# GaN-amplifier.net
KiCad netlist of a schematic drawn in EAGLE
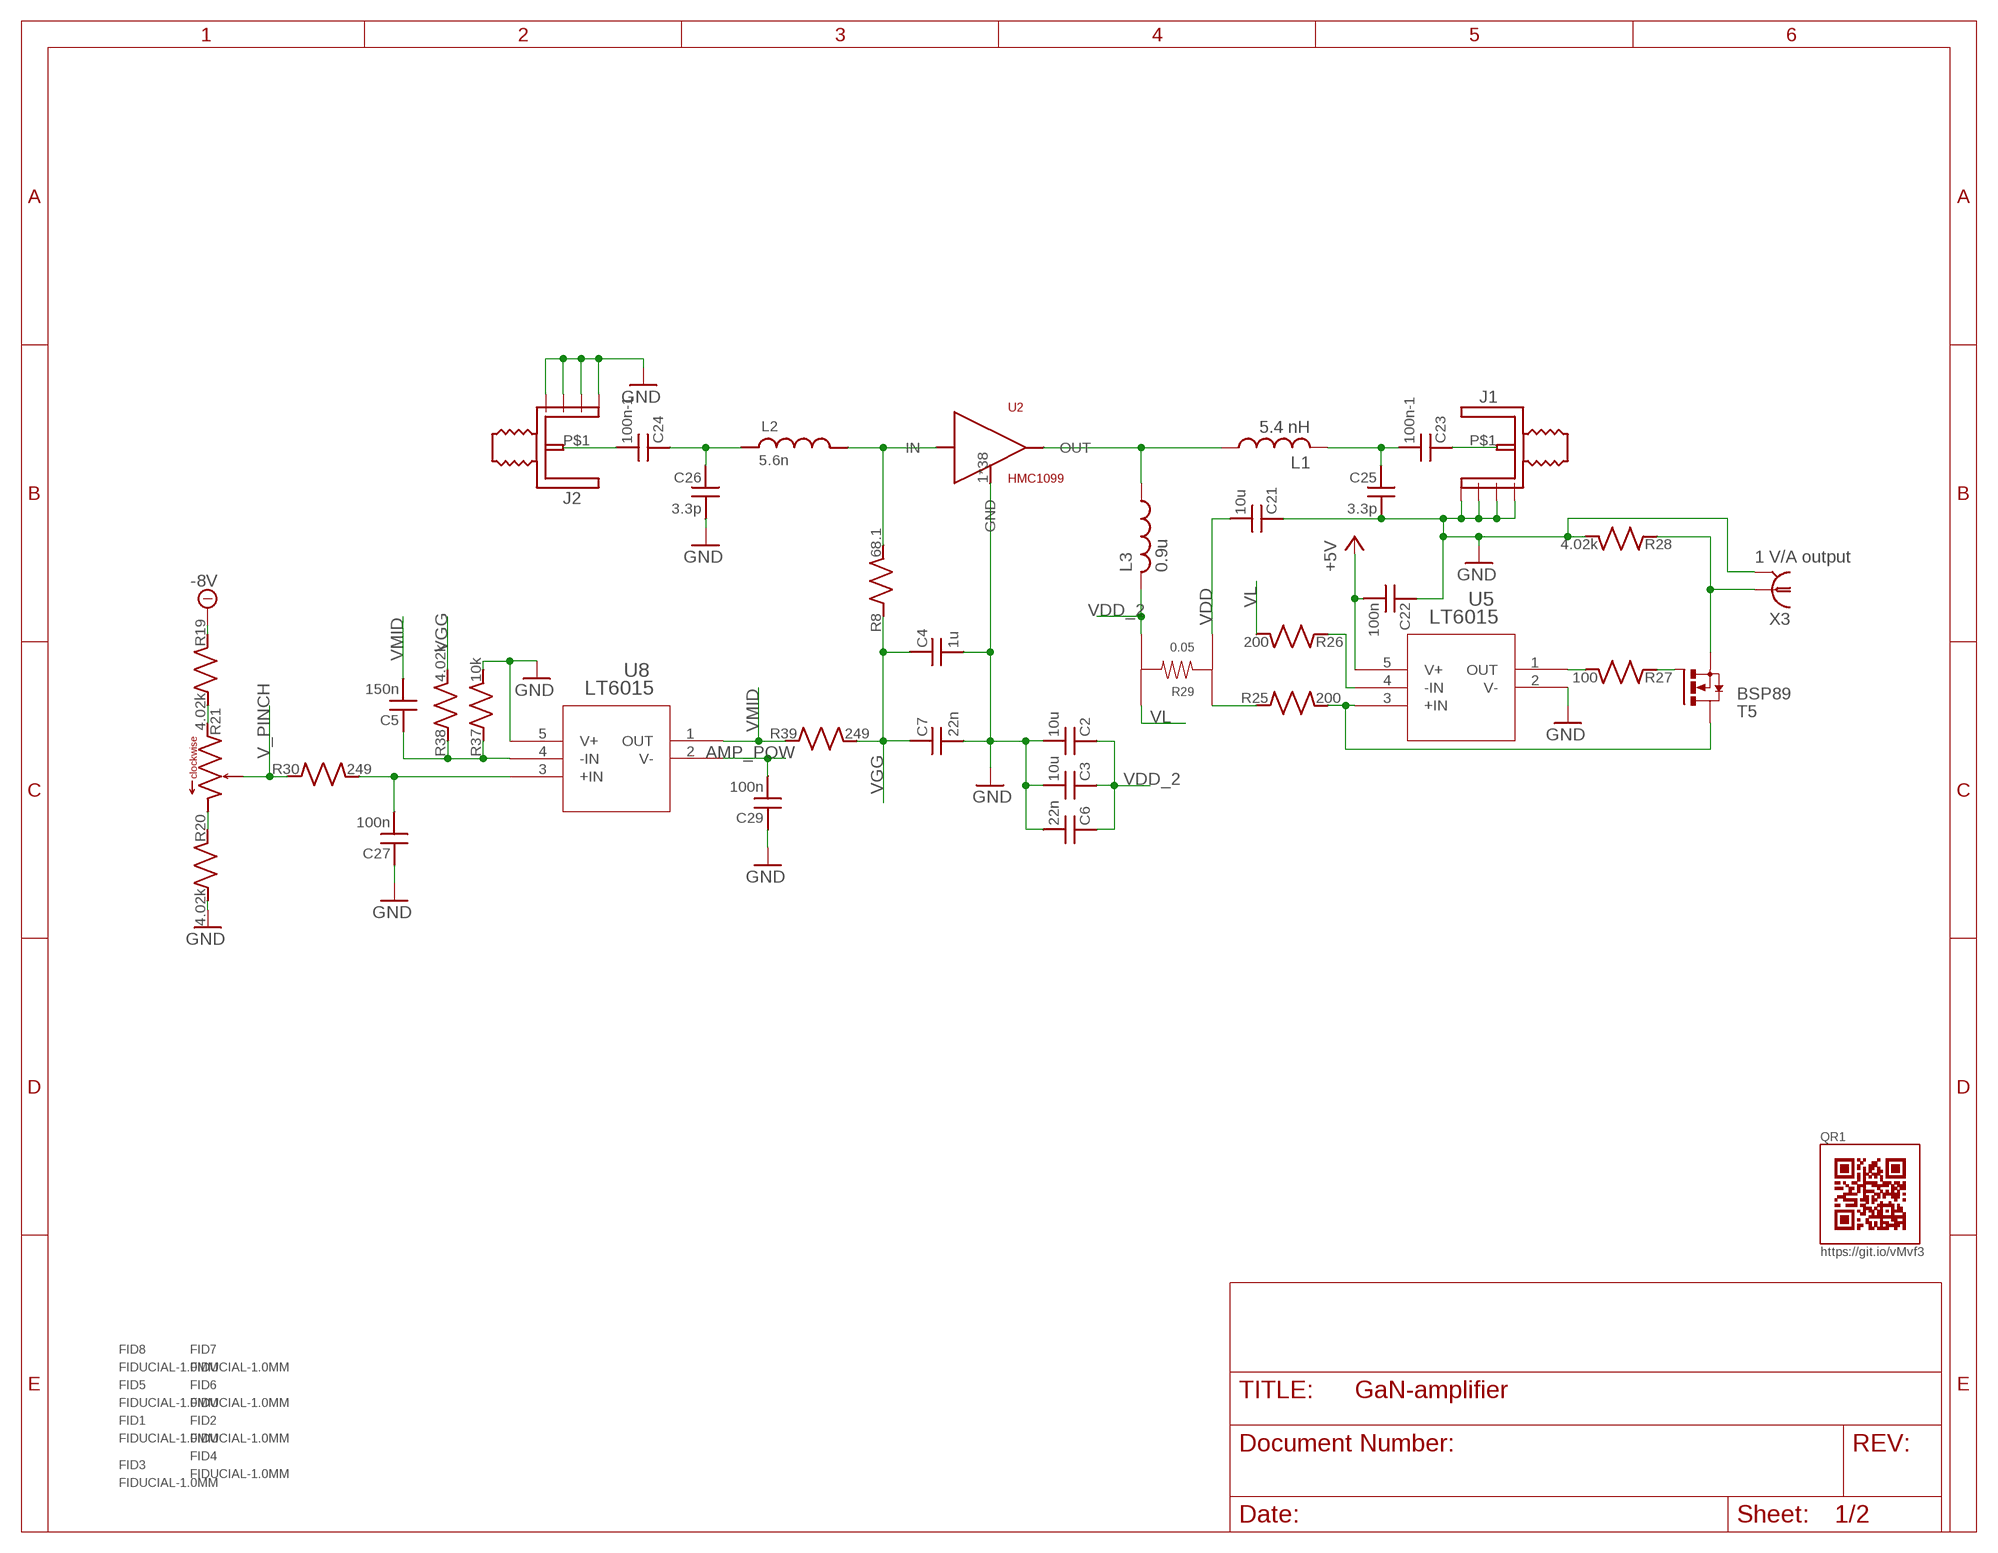
[diagram p0: schematic, sheet 1]
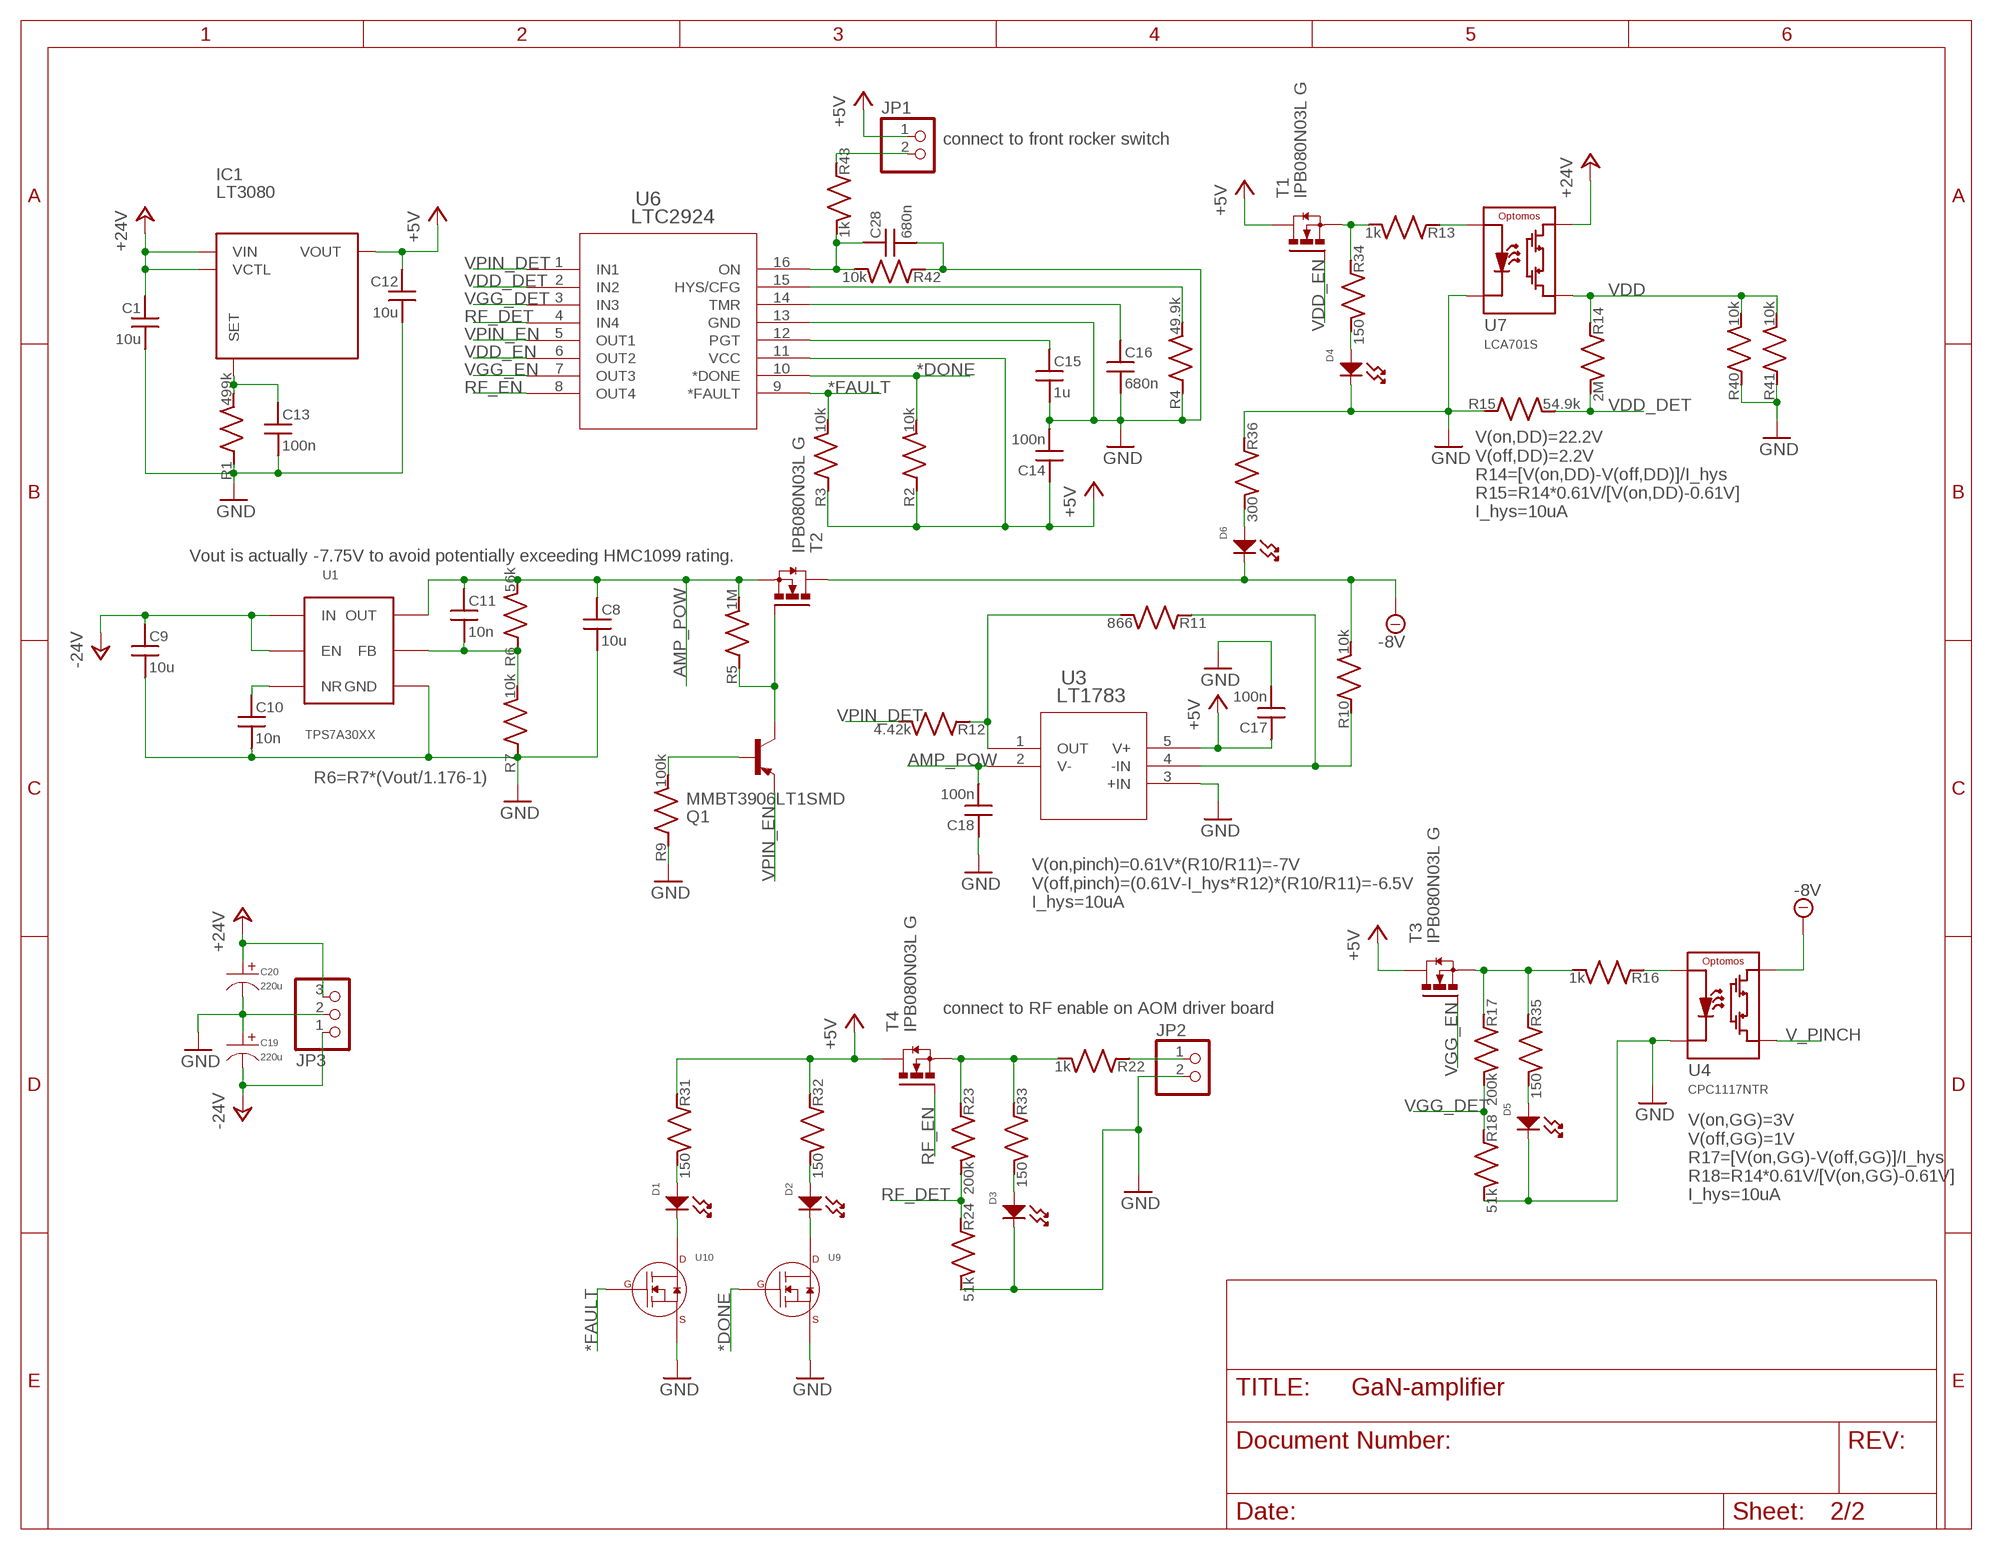
[diagram p1: schematic, sheet 2]

(export (version "E")
  (design (tool "Eeschema 10.0.6"))
  (components
    (comp (ref "C1")
      (value "10u")
      (footprint "eagle-import:C_MLCC_1210")
      (fields (field (name "PARTNO") "CL32B106KBJNNNE"))
      (libsource (lib "eagle-import") (part "C_MLCC_SMDCMLCC_1210"))
    )
    (comp (ref "C8")
      (value "10u")
      (footprint "eagle-import:C_MLCC_1210")
      (fields (field (name "PARTNO") "CL32B106KBJNNNE"))
      (libsource (lib "eagle-import") (part "C_MLCC_SMDCMLCC_1210"))
    )
    (comp (ref "C9")
      (value "10u")
      (footprint "eagle-import:C_MLCC_1210")
      (fields (field (name "PARTNO") "CL32B106KBJNNNE"))
      (libsource (lib "eagle-import") (part "C_MLCC_SMDCMLCC_1210"))
    )
    (comp (ref "C10")
      (value "10n")
      (footprint "eagle-import:C_MLCC_0402")
      (fields (field (name "PARTNO") "CL05B103KB5NNNC"))
      (libsource (lib "eagle-import") (part "C_MLCC_SMDCMLCC_0402"))
    )
    (comp (ref "C11")
      (value "10n")
      (footprint "eagle-import:C_MLCC_0402")
      (fields (field (name "PARTNO") "CL05B103KB5NNNC"))
      (libsource (lib "eagle-import") (part "C_MLCC_SMDCMLCC_0402"))
    )
    (comp (ref "C12")
      (value "10u")
      (footprint "eagle-import:C_MLCC_1210")
      (fields (field (name "PARTNO") "CL32B106KBJNNNE"))
      (libsource (lib "eagle-import") (part "C_MLCC_SMDCMLCC_1210"))
    )
    (comp (ref "C13")
      (value "100n")
      (footprint "eagle-import:C_MLCC_0603")
      (fields (field (name "PARTNO") "CL10B104KB8SFNC"))
      (libsource (lib "eagle-import") (part "C_MLCC_SMDCMLCC_0603"))
    )
    (comp (ref "C14")
      (value "100n")
      (footprint "eagle-import:C_MLCC_0603")
      (fields (field (name "PARTNO") "CL10B104KB8SFNC"))
      (libsource (lib "eagle-import") (part "C_MLCC_SMDCMLCC_0603"))
    )
    (comp (ref "C15")
      (value "1u")
      (footprint "eagle-import:C_MLCC_0603")
      (fields (field (name "PARTNO") "CL10B105KA8NNNC"))
      (libsource (lib "eagle-import") (part "C_MLCC_SMDCMLCC_0603"))
    )
    (comp (ref "C16")
      (value "680n")
      (footprint "eagle-import:C_MLCC_0603")
      (fields (field (name "PARTNO") "CL10B684KO8NFNC"))
      (libsource (lib "eagle-import") (part "C_MLCC_SMDCMLCC_0603"))
    )
    (comp (ref "C17")
      (value "100n")
      (footprint "eagle-import:C_MLCC_0603")
      (fields (field (name "PARTNO") "CL10B104KB8SFNC"))
      (libsource (lib "eagle-import") (part "C_MLCC_SMDCMLCC_0603"))
    )
    (comp (ref "C18")
      (value "100n")
      (footprint "eagle-import:C_MLCC_0603")
      (fields (field (name "PARTNO") "CL10B104KB8SFNC"))
      (libsource (lib "eagle-import") (part "C_MLCC_SMDCMLCC_0603"))
    )
    (comp (ref "C19")
      (value "220u")
      (footprint "eagle-import:CP10MM")
      (fields (field (name "PARTNO") "MF-CAP-10MM-220uF"))
      (libsource (lib "eagle-import") (part "CAPACITOR_P_10MM"))
    )
    (comp (ref "C20")
      (value "220u")
      (footprint "eagle-import:CP10MM")
      (fields (field (name "PARTNO") "MF-CAP-10MM-220uF"))
      (libsource (lib "eagle-import") (part "CAPACITOR_P_10MM"))
    )
    (comp (ref "C28")
      (value "680n")
      (footprint "eagle-import:C_MLCC_0603")
      (fields (field (name "PARTNO") "CL10B684KO8NFNC"))
      (libsource (lib "eagle-import") (part "C_MLCC_SMDCMLCC_0603"))
    )
    (comp (ref "D1")
      (value "LED_SINGLE-0603-GREEN")
      (footprint "eagle-import:LED0603")
      (fields (field (name "HOUSEPART") "YES") (field (name "MPN") "MF-LED-0603-GREEN"))
      (libsource (lib "eagle-import") (part "LED_SINGLE-0603-GREEN"))
    )
    (comp (ref "D2")
      (value "LED_SINGLE-0603-RED")
      (footprint "eagle-import:LED0603")
      (fields (field (name "HOUSEPART") "YES") (field (name "MPN") "MF-LED-0603-RED"))
      (libsource (lib "eagle-import") (part "LED_SINGLE-0603-RED"))
    )
    (comp (ref "D3")
      (value "LED_SINGLE-0603-GREEN")
      (footprint "eagle-import:LED0603")
      (fields (field (name "HOUSEPART") "YES") (field (name "MPN") "MF-LED-0603-GREEN"))
      (libsource (lib "eagle-import") (part "LED_SINGLE-0603-GREEN"))
    )
    (comp (ref "D4")
      (value "LED_SINGLE-0603-GREEN")
      (footprint "eagle-import:LED0603")
      (fields (field (name "HOUSEPART") "YES") (field (name "MPN") "MF-LED-0603-GREEN"))
      (libsource (lib "eagle-import") (part "LED_SINGLE-0603-GREEN"))
    )
    (comp (ref "D5")
      (value "LED_SINGLE-0603-GREEN")
      (footprint "eagle-import:LED0603")
      (fields (field (name "HOUSEPART") "YES") (field (name "MPN") "MF-LED-0603-GREEN"))
      (libsource (lib "eagle-import") (part "LED_SINGLE-0603-GREEN"))
    )
    (comp (ref "D6")
      (value "LED_SINGLE-0603-GREEN")
      (footprint "eagle-import:LED0603")
      (fields (field (name "HOUSEPART") "YES") (field (name "MPN") "MF-LED-0603-GREEN"))
      (libsource (lib "eagle-import") (part "LED_SINGLE-0603-GREEN"))
    )
    (comp (ref "IC1")
      (value "LT3080")
      (footprint "eagle-import:TO263-5")
      (fields (field (name "PARTNO") "LT3080EQ#PBF"))
      (libsource (lib "eagle-import") (part "LT3080"))
    )
    (comp (ref "JP1")
      (value "PINHD-1X2")
      (footprint "eagle-import:1X02")
      (fields (field (name "PARTNO") "640456-2"))
      (libsource (lib "eagle-import") (part "PINHD-1X2"))
    )
    (comp (ref "JP2")
      (value "PINHD-1X2")
      (footprint "eagle-import:1X02")
      (fields (field (name "PARTNO") "640456-2"))
      (libsource (lib "eagle-import") (part "PINHD-1X2"))
    )
    (comp (ref "JP3")
      (value "PINHD-1X3")
      (footprint "eagle-import:1X03")
      (fields (field (name "PARTNO") "640456-3"))
      (libsource (lib "eagle-import") (part "PINHD-1X3"))
    )
    (comp (ref "Q1")
      (value "MMBT3906LT1SMD")
      (footprint "eagle-import:SOT23-BEC")
      (fields (field (name "PARTNO") "MF-DSC-SOT233-MMBT3906"))
      (libsource (lib "eagle-import") (part "MMBT3906SMDLT1"))
    )
    (comp (ref "R1")
      (value "499k")
      (footprint "eagle-import:R_0603")
      (fields (field (name "PARTNO") "ERJ-3EKF4993V"))
      (libsource (lib "eagle-import") (part "R_SMDR0603"))
    )
    (comp (ref "R2")
      (value "10k")
      (footprint "eagle-import:R_0603")
      (fields (field (name "PARTNO") "ERJ-3EKF1002V"))
      (libsource (lib "eagle-import") (part "R_SMDR0603"))
    )
    (comp (ref "R3")
      (value "10k")
      (footprint "eagle-import:R_0603")
      (fields (field (name "PARTNO") "ERJ-3EKF1002V"))
      (libsource (lib "eagle-import") (part "R_SMDR0603"))
    )
    (comp (ref "R4")
      (value "49.9k")
      (footprint "eagle-import:R_0603")
      (fields (field (name "PARTNO") "ERJ-3EKF4992V"))
      (libsource (lib "eagle-import") (part "R_SMDR0603"))
    )
    (comp (ref "R5")
      (value "1M")
      (footprint "eagle-import:R_0603")
      (fields (field (name "PARTNO") "ERJ-3EKF1004V"))
      (libsource (lib "eagle-import") (part "R_SMDR0603"))
    )
    (comp (ref "R6")
      (value "56k")
      (footprint "eagle-import:R_0402")
      (fields (field (name "PARTNO") "ERJ-2RKF5602X"))
      (libsource (lib "eagle-import") (part "R_SMDR0402"))
    )
    (comp (ref "R7")
      (value "10k")
      (footprint "eagle-import:R_0402")
      (fields (field (name "PARTNO") "ERJ-2RKF1002X"))
      (libsource (lib "eagle-import") (part "R_SMDR0402"))
    )
    (comp (ref "R9")
      (value "100k")
      (footprint "eagle-import:R_0603")
      (fields (field (name "PARTNO") "ERJ-3EKF1003V"))
      (libsource (lib "eagle-import") (part "R_SMDR0603"))
    )
    (comp (ref "R10")
      (value "10k")
      (footprint "eagle-import:R_0603")
      (fields (field (name "PARTNO") "ERJ-3EKF1002V"))
      (libsource (lib "eagle-import") (part "R_SMDR0603"))
    )
    (comp (ref "R11")
      (value "866")
      (footprint "eagle-import:R_0603")
      (fields (field (name "PARTNO") "ERJ-3EKF8660V"))
      (libsource (lib "eagle-import") (part "R_SMDR0603"))
    )
    (comp (ref "R12")
      (value "4.42k")
      (footprint "eagle-import:R_0603")
      (fields (field (name "PARTNO") "ERJ-3EKF4421V"))
      (libsource (lib "eagle-import") (part "R_SMDR0603"))
    )
    (comp (ref "R13")
      (value "1k")
      (footprint "eagle-import:R_0603")
      (fields (field (name "PARTNO") "ERJ-3EKF1001V"))
      (libsource (lib "eagle-import") (part "R_SMDR0603"))
    )
    (comp (ref "R14")
      (value "2M")
      (footprint "eagle-import:R_0603")
      (fields (field (name "PARTNO") "ERJ-3EKF2004V"))
      (libsource (lib "eagle-import") (part "R_SMDR0603"))
    )
    (comp (ref "R15")
      (value "54.9k")
      (footprint "eagle-import:R_0603")
      (fields (field (name "PARTNO") "ERJ-3EKF5492V"))
      (libsource (lib "eagle-import") (part "R_SMDR0603"))
    )
    (comp (ref "R16")
      (value "1k")
      (footprint "eagle-import:R_0603")
      (fields (field (name "PARTNO") "ERJ-3EKF1001V"))
      (libsource (lib "eagle-import") (part "R_SMDR0603"))
    )
    (comp (ref "R17")
      (value "200k")
      (footprint "eagle-import:R_0603")
      (fields (field (name "PARTNO") "ERJ-3EKF2003V"))
      (libsource (lib "eagle-import") (part "R_SMDR0603"))
    )
    (comp (ref "R18")
      (value "51k")
      (footprint "eagle-import:R_0603")
      (fields (field (name "PARTNO") "ERJ-3EKF5102V"))
      (libsource (lib "eagle-import") (part "R_SMDR0603"))
    )
    (comp (ref "R22")
      (value "1k")
      (footprint "eagle-import:R_0603")
      (fields (field (name "PARTNO") "ERJ-3EKF1001V"))
      (libsource (lib "eagle-import") (part "R_SMDR0603"))
    )
    (comp (ref "R23")
      (value "200k")
      (footprint "eagle-import:R_0603")
      (fields (field (name "PARTNO") "ERJ-3EKF2003V"))
      (libsource (lib "eagle-import") (part "R_SMDR0603"))
    )
    (comp (ref "R24")
      (value "51k")
      (footprint "eagle-import:R_0603")
      (fields (field (name "PARTNO") "ERJ-3EKF5102V"))
      (libsource (lib "eagle-import") (part "R_SMDR0603"))
    )
    (comp (ref "R31")
      (value "150")
      (footprint "eagle-import:R_0603")
      (fields (field (name "PARTNO") "ERJ-3EKF1500V"))
      (libsource (lib "eagle-import") (part "R_SMDR0603"))
    )
    (comp (ref "R32")
      (value "150")
      (footprint "eagle-import:R_0603")
      (fields (field (name "PARTNO") "ERJ-3EKF1500V"))
      (libsource (lib "eagle-import") (part "R_SMDR0603"))
    )
    (comp (ref "R33")
      (value "150")
      (footprint "eagle-import:R_0603")
      (fields (field (name "PARTNO") "ERJ-3EKF1500V"))
      (libsource (lib "eagle-import") (part "R_SMDR0603"))
    )
    (comp (ref "R34")
      (value "150")
      (footprint "eagle-import:R_0603")
      (fields (field (name "PARTNO") "ERJ-3EKF1500V"))
      (libsource (lib "eagle-import") (part "R_SMDR0603"))
    )
    (comp (ref "R35")
      (value "150")
      (footprint "eagle-import:R_0603")
      (fields (field (name "PARTNO") "ERJ-3EKF1500V"))
      (libsource (lib "eagle-import") (part "R_SMDR0603"))
    )
    (comp (ref "R36")
      (value "300")
      (footprint "eagle-import:R_0603")
      (fields (field (name "PARTNO") "ERJ-PA3F3000V"))
      (libsource (lib "eagle-import") (part "R_SMDR0603"))
    )
    (comp (ref "R40")
      (value "10k")
      (footprint "eagle-import:R_0603")
      (fields (field (name "PARTNO") "ERJ-3EKF1002V"))
      (libsource (lib "eagle-import") (part "R_SMDR0603"))
    )
    (comp (ref "R41")
      (value "10k")
      (footprint "eagle-import:R_0603")
      (fields (field (name "PARTNO") "ERJ-3EKF1002V"))
      (libsource (lib "eagle-import") (part "R_SMDR0603"))
    )
    (comp (ref "R42")
      (value "10k")
      (footprint "eagle-import:R_0603")
      (fields (field (name "PARTNO") "ERJ-3EKF1002V"))
      (libsource (lib "eagle-import") (part "R_SMDR0603"))
    )
    (comp (ref "R43")
      (value "1k")
      (footprint "eagle-import:R_0603")
      (fields (field (name "PARTNO") "ERJ-3EKF1001V"))
      (libsource (lib "eagle-import") (part "R_SMDR0603"))
    )
    (comp (ref "T1")
      (value "IPB080N03L G")
      (footprint "eagle-import:D2PACK")
      (libsource (lib "eagle-import") (part "IRL3714"))
    )
    (comp (ref "T2")
      (value "IPB080N03L G")
      (footprint "eagle-import:D2PACK")
      (libsource (lib "eagle-import") (part "IRL3714"))
    )
    (comp (ref "T3")
      (value "IPB080N03L G")
      (footprint "eagle-import:D2PACK")
      (libsource (lib "eagle-import") (part "IRL3714"))
    )
    (comp (ref "T4")
      (value "IPB080N03L G")
      (footprint "eagle-import:D2PACK")
      (libsource (lib "eagle-import") (part "IRL3714"))
    )
    (comp (ref "U1")
      (value "TPS7A30XX")
      (footprint "eagle-import:DGN")
      (fields (field (name "PARTNO") "TPS7A3001DGNR"))
      (libsource (lib "eagle-import") (part "TPS7A30XX"))
    )
    (comp (ref "U3")
      (value "LT1783")
      (footprint "eagle-import:TSOT-23_S5")
      (fields
        (field (name "MANUFACTURER_PART_NUMBER") "lt1783hs5")
        (field (name "PARTNO") "LT1783HS5#TRMPBF")
        (field (name "COPYRIGHT") "Copyright C 2016 Accelerated Designs. All rights reserved")
      )
      (libsource (lib "eagle-import") (part "LT1783HS5"))
    )
    (comp (ref "U4")
      (value "CPC1117NTR")
      (footprint "eagle-import:4-LEAD_SOP")
      (libsource (lib "eagle-import") (part "CPC1117NTR"))
    )
    (comp (ref "U6")
      (value "LTC2924")
      (footprint "eagle-import:SSOP-16_GN")
      (fields (field (name "MANUFACTURER_PART_NUMBER") "ltc2924ign") (field (name "PARTNO") "LTC2924IGN#PBF"))
      (libsource (lib "eagle-import") (part "LTC2924IGN"))
    )
    (comp (ref "U7")
      (value "LCA701S")
      (footprint "eagle-import:6-LEAD_SMT")
      (libsource (lib "eagle-import") (part "LCA701S"))
    )
    (comp (ref "U9")
      (value "N-CHANNEL_FET_BSS138_SOT-23-3")
      (footprint "eagle-import:SOT-23-3")
      (fields (field (name "HOUSEPART") "YES") (field (name "MPN") "MF-DSC-SOT233-BSS138"))
      (libsource (lib "eagle-import") (part "N-CHANNEL_FET_SOT-23-3_BSS138"))
    )
    (comp (ref "U10")
      (value "N-CHANNEL_FET_BSS138_SOT-23-3")
      (footprint "eagle-import:SOT-23-3")
      (fields (field (name "HOUSEPART") "YES") (field (name "MPN") "MF-DSC-SOT233-BSS138"))
      (libsource (lib "eagle-import") (part "N-CHANNEL_FET_SOT-23-3_BSS138"))
    )
    (comp (ref "C2")
      (value "10u")
      (footprint "eagle-import:C_MLCC_1210")
      (fields (field (name "PARTNO") "CL32B106KBJNNNE"))
      (libsource (lib "eagle-import") (part "C_MLCC_SMDCMLCC_1210"))
    )
    (comp (ref "C3")
      (value "10u")
      (footprint "eagle-import:C_MLCC_1210")
      (fields (field (name "PARTNO") "CL32B106KBJNNNE"))
      (libsource (lib "eagle-import") (part "C_MLCC_SMDCMLCC_1210"))
    )
    (comp (ref "C4")
      (value "1u")
      (footprint "eagle-import:C_MLCC_0603")
      (fields (field (name "PARTNO") "CL10B105KA8NNNC"))
      (libsource (lib "eagle-import") (part "C_MLCC_SMDCMLCC_0603"))
    )
    (comp (ref "C5")
      (value "150n")
      (footprint "eagle-import:C_MLCC_0603")
      (fields (field (name "PARTNO") "CL10B154KO8NNNC"))
      (libsource (lib "eagle-import") (part "C_MLCC_SMDCMLCC_0603"))
    )
    (comp (ref "C6")
      (value "22n")
      (footprint "eagle-import:C_MLCC_0603")
      (fields (field (name "PARTNO") "CL10B223KB8NNNC"))
      (libsource (lib "eagle-import") (part "C_MLCC_SMDCMLCC_0603"))
    )
    (comp (ref "C7")
      (value "22n")
      (footprint "eagle-import:C_MLCC_0603")
      (fields (field (name "PARTNO") "CL10B223KB8NNNC"))
      (libsource (lib "eagle-import") (part "C_MLCC_SMDCMLCC_0603"))
    )
    (comp (ref "C21")
      (value "10u")
      (footprint "eagle-import:C_MLCC_1210")
      (fields (field (name "PARTNO") "CL32B106KBJNNNE"))
      (libsource (lib "eagle-import") (part "C_MLCC_SMDCMLCC_1210"))
    )
    (comp (ref "C22")
      (value "100n")
      (footprint "eagle-import:C_MLCC_0603")
      (fields (field (name "PARTNO") "CL10B104KB8SFNC"))
      (libsource (lib "eagle-import") (part "C_MLCC_SMDCMLCC_0603"))
    )
    (comp (ref "C23")
      (value "100n-1")
      (footprint "eagle-import:C_MLCC_0402")
      (fields (field (name "PARTNO") "0402BB104KW500"))
      (libsource (lib "eagle-import") (part "C_MLCC_SMDCMLCC_0402"))
    )
    (comp (ref "C24")
      (value "100n-1")
      (footprint "eagle-import:C_MLCC_0402")
      (fields (field (name "PARTNO") "0402BB104KW500"))
      (libsource (lib "eagle-import") (part "C_MLCC_SMDCMLCC_0402"))
    )
    (comp (ref "C25")
      (value "3.3p")
      (footprint "eagle-import:C_MLCC_0603")
      (fields (field (name "PARTNO") "600S3R3CT250XT"))
      (libsource (lib "eagle-import") (part "C_MLCC_SMDCMLCC_0603"))
    )
    (comp (ref "C26")
      (value "3.3p")
      (footprint "eagle-import:C_MLCC_0603")
      (fields (field (name "PARTNO") "600S3R3CT250XT"))
      (libsource (lib "eagle-import") (part "C_MLCC_SMDCMLCC_0603"))
    )
    (comp (ref "C27")
      (value "100n")
      (footprint "eagle-import:C_MLCC_0603")
      (fields (field (name "PARTNO") "CL10B104KB8SFNC"))
      (libsource (lib "eagle-import") (part "C_MLCC_SMDCMLCC_0603"))
    )
    (comp (ref "C29")
      (value "100n")
      (footprint "eagle-import:C_MLCC_0603")
      (fields (field (name "PARTNO") "CL10B104KB8SFNC"))
      (libsource (lib "eagle-import") (part "C_MLCC_SMDCMLCC_0603"))
    )
    (comp (ref "FID1")
      (value "FIDUCIAL-1.0MM")
      (footprint "eagle-import:FID_1.0MM")
      (libsource (lib "eagle-import") (part "FIDUCIAL-1.0MM"))
    )
    (comp (ref "FID2")
      (value "FIDUCIAL-1.0MM")
      (footprint "eagle-import:FID_1.0MM")
      (libsource (lib "eagle-import") (part "FIDUCIAL-1.0MM"))
    )
    (comp (ref "FID3")
      (value "FIDUCIAL-1.0MM")
      (footprint "eagle-import:FID_1.0MM")
      (libsource (lib "eagle-import") (part "FIDUCIAL-1.0MM"))
    )
    (comp (ref "FID4")
      (value "FIDUCIAL-1.0MM")
      (footprint "eagle-import:FID_1.0MM")
      (libsource (lib "eagle-import") (part "FIDUCIAL-1.0MM"))
    )
    (comp (ref "FID5")
      (value "FIDUCIAL-1.0MM")
      (footprint "eagle-import:FID_1.0MM")
      (libsource (lib "eagle-import") (part "FIDUCIAL-1.0MM"))
    )
    (comp (ref "FID6")
      (value "FIDUCIAL-1.0MM")
      (footprint "eagle-import:FID_1.0MM")
      (libsource (lib "eagle-import") (part "FIDUCIAL-1.0MM"))
    )
    (comp (ref "FID7")
      (value "FIDUCIAL-1.0MM")
      (footprint "eagle-import:FID_1.0MM")
      (libsource (lib "eagle-import") (part "FIDUCIAL-1.0MM"))
    )
    (comp (ref "FID8")
      (value "FIDUCIAL-1.0MM")
      (footprint "eagle-import:FID_1.0MM")
      (libsource (lib "eagle-import") (part "FIDUCIAL-1.0MM"))
    )
    (comp (ref "J1")
      (value "JOHNSON_SMA_EDGE_LAUNCH_142-0701-851")
      (footprint "eagle-import:JOHNSON_SMA_EDGE_LAUNCH_142-0701-851")
      (fields (field (name "PARTNO") "142-0701-851"))
      (libsource (lib "eagle-import") (part "JOHNSON_SMA_EDGE_LAUNCH_142-0701-851"))
    )
    (comp (ref "J2")
      (value "JOHNSON_SMA_EDGE_LAUNCH_142-0701-851")
      (footprint "eagle-import:JOHNSON_SMA_EDGE_LAUNCH_142-0701-851")
      (fields (field (name "PARTNO") "142-0701-851"))
      (libsource (lib "eagle-import") (part "JOHNSON_SMA_EDGE_LAUNCH_142-0701-851"))
    )
    (comp (ref "L1")
      (value "5.4 nH")
      (footprint "eagle-import:0906")
      (fields (field (name "PARTNO") "0906-5JLB"))
      (libsource (lib "eagle-import") (part "0906-XX"))
    )
    (comp (ref "L2")
      (value "5.6n")
      (footprint "eagle-import:R_0402")
      (fields (field (name "PARTNO") "0402CS-5N6XJLU"))
      (libsource (lib "eagle-import") (part "L_FERRITE_SMDLFERRITE_0402"))
    )
    (comp (ref "L3")
      (value "0.9u")
      (footprint "eagle-import:1008")
      (fields (field (name "PARTNO") "1008AF-901XKLC"))
      (libsource (lib "eagle-import") (part "1008AF-XX"))
    )
    (comp (ref "QR1")
      (value "QR-HTTPS://GIT.IO/VMVF3-LIGHT-SILK")
      (footprint "eagle-import:QR-HTTPS___GIT.IO_VMVF3-LIGHT-SILK")
      (libsource (lib "eagle-import") (part "QR-HTTPS{colon}//GIT.IO/VMVF3-LIGHT-SILK"))
    )
    (comp (ref "R8")
      (value "68.1")
      (footprint "eagle-import:R_0603")
      (fields (field (name "PARTNO") "ERJ-3EKF68R1V"))
      (libsource (lib "eagle-import") (part "R_SMDR0603"))
    )
    (comp (ref "R19")
      (value "4.02k")
      (footprint "eagle-import:R_0603")
      (fields (field (name "PARTNO") "TNPW06034K02BEEA"))
      (libsource (lib "eagle-import") (part "R_SMDR0603"))
    )
    (comp (ref "R20")
      (value "4.02k")
      (footprint "eagle-import:R_0603")
      (fields (field (name "PARTNO") "TNPW06034K02BEEA"))
      (libsource (lib "eagle-import") (part "R_SMDR0603"))
    )
    (comp (ref "R21")
      (value "R_TRIM")
      (footprint "eagle-import:RJ24")
      (fields (field (name "PARTNO") "Y006910K0000J9L"))
      (libsource (lib "eagle-import") (part "R_TRIM"))
    )
    (comp (ref "R25")
      (value "200")
      (footprint "eagle-import:R_0603")
      (fields (field (name "PARTNO") "TNPW0603200RBEEA"))
      (libsource (lib "eagle-import") (part "R_SMDR0603"))
    )
    (comp (ref "R26")
      (value "200")
      (footprint "eagle-import:R_0603")
      (fields (field (name "PARTNO") "TNPW0603200RBEEA"))
      (libsource (lib "eagle-import") (part "R_SMDR0603"))
    )
    (comp (ref "R27")
      (value "100")
      (footprint "eagle-import:R_0603")
      (fields (field (name "PARTNO") "ERJ-3EKF1000V"))
      (libsource (lib "eagle-import") (part "R_SMDR0603"))
    )
    (comp (ref "R28")
      (value "4.02k")
      (footprint "eagle-import:R_0603")
      (fields (field (name "PARTNO") "TNPW06034K02BEEA"))
      (libsource (lib "eagle-import") (part "R_SMDR0603"))
    )
    (comp (ref "R29")
      (value "0.05")
      (footprint "eagle-import:1206_KELVIN")
      (fields (field (name "PARTNO") "LVK12R050DER"))
      (libsource (lib "eagle-import") (part "RES_KELVIN"))
    )
    (comp (ref "R30")
      (value "249")
      (footprint "eagle-import:R_0603")
      (fields (field (name "PARTNO") "TNPW0603249RBEEA"))
      (libsource (lib "eagle-import") (part "R_SMDR0603"))
    )
    (comp (ref "R37")
      (value "10k")
      (footprint "eagle-import:R_0603")
      (fields (field (name "PARTNO") "TNPW060310K0BEEA"))
      (libsource (lib "eagle-import") (part "R_SMDR0603"))
    )
    (comp (ref "R38")
      (value "4.02k")
      (footprint "eagle-import:R_0603")
      (fields (field (name "PARTNO") "TNPW06034K02BEEA"))
      (libsource (lib "eagle-import") (part "R_SMDR0603"))
    )
    (comp (ref "R39")
      (value "249")
      (footprint "eagle-import:R_0603")
      (fields (field (name "PARTNO") "TNPW0603249RBEEA"))
      (libsource (lib "eagle-import") (part "R_SMDR0603"))
    )
    (comp (ref "T5")
      (value "BSP89")
      (footprint "eagle-import:PG-SOT-223")
      (fields (field (name "PARTNO") "BSP89H6327XTSA1"))
      (libsource (lib "eagle-import") (part "BSP89"))
    )
    (comp (ref "U2")
      (value "HMC1099")
      (footprint "eagle-import:HCP-32-2")
      (fields (field (name "PARTNO") "HMC1099LP5DE"))
      (libsource (lib "eagle-import") (part "HMC1099"))
    )
    (comp (ref "U5")
      (value "LT6015")
      (footprint "eagle-import:TSOT-23_S5")
      (fields (field (name "PARTNO") "LT6015HS5#TRMPBF"))
      (libsource (lib "eagle-import") (part "LT6015HS5"))
    )
    (comp (ref "U8")
      (value "LT6015")
      (footprint "eagle-import:TSOT-23_S5")
      (fields (field (name "PARTNO") "LT6015HS5#TRMPBF"))
      (libsource (lib "eagle-import") (part "LT6015HS5"))
    )
    (comp (ref "X3")
      (value "BNC-V")
      (footprint "eagle-import:BNC-V")
      (fields (field (name "PARTNO") "5227222-3"))
      (libsource (lib "eagle-import") (part "BNC-V"))
    )
  )
  (nets
    (net (code "1") (name "*DONE") (class "Default")
      (node (ref "R2") (pin "P$2") (pinfunction "2_P$2") (pintype "passive"))
      (node (ref "U6") (pin "10") (pinfunction "*DONE_10") (pintype "output"))
      (node (ref "U9") (pin "P$1") (pinfunction "GATE_P$1") (pintype "bidirectional"))
    )
    (net (code "2") (name "*FAULT") (class "Default")
      (node (ref "R3") (pin "P$2") (pinfunction "2_P$2") (pintype "passive"))
      (node (ref "U10") (pin "P$1") (pinfunction "GATE_P$1") (pintype "bidirectional"))
      (node (ref "U6") (pin "9") (pinfunction "*FAULT_9") (pintype "passive"))
    )
    (net (code "3") (name "+5V") (class "Default")
      (node (ref "C12") (pin "P$1") (pinfunction "1_P$1") (pintype "passive"))
      (node (ref "C14") (pin "P$1") (pinfunction "1_P$1") (pintype "passive"))
      (node (ref "C17") (pin "P$1") (pinfunction "1_P$1") (pintype "passive"))
      (node (ref "C22") (pin "P$2") (pinfunction "2_P$2") (pintype "passive"))
      (node (ref "IC1") (pin "3") (pinfunction "VOUT_3") (pintype "bidirectional"))
      (node (ref "IC1") (pin "6") (pinfunction "VOUT_6") (pintype "bidirectional"))
      (node (ref "JP1") (pin "1") (pinfunction "1_1") (pintype "passive"))
      (node (ref "R2") (pin "P$1") (pinfunction "1_P$1") (pintype "passive"))
      (node (ref "R3") (pin "P$1") (pinfunction "1_P$1") (pintype "passive"))
      (node (ref "R31") (pin "P$1") (pinfunction "1_P$1") (pintype "passive"))
      (node (ref "R32") (pin "P$1") (pinfunction "1_P$1") (pintype "passive"))
      (node (ref "T1") (pin "2") (pinfunction "D_2") (pintype "passive"))
      (node (ref "T3") (pin "2") (pinfunction "D_2") (pintype "passive"))
      (node (ref "T4") (pin "2") (pinfunction "D_2") (pintype "passive"))
      (node (ref "U3") (pin "5") (pinfunction "V+_5") (pintype "power_in"))
      (node (ref "U5") (pin "5") (pinfunction "V+_5") (pintype "power_in"))
      (node (ref "U6") (pin "11") (pinfunction "VCC_11") (pintype "power_in"))
    )
    (net (code "4") (name "+24V") (class "Default")
      (node (ref "C1") (pin "P$1") (pinfunction "1_P$1") (pintype "passive"))
      (node (ref "C20") (pin "P$1") (pinfunction "P$1_P$1") (pintype "passive"))
      (node (ref "IC1") (pin "4") (pinfunction "VCTL_4") (pintype "bidirectional"))
      (node (ref "IC1") (pin "5") (pinfunction "VIN_5") (pintype "bidirectional"))
      (node (ref "JP3") (pin "3") (pinfunction "3_3") (pintype "passive"))
      (node (ref "U7") (pin "6") (pinfunction "L+_6") (pintype "bidirectional"))
    )
    (net (code "5") (name "-8V") (class "Default")
      (node (ref "D6") (pin "CATHODE") (pinfunction "CATHODE_CATHODE") (pintype "power_in"))
      (node (ref "R10") (pin "P$2") (pinfunction "2_P$2") (pintype "passive"))
      (node (ref "R19") (pin "P$1") (pinfunction "1_P$1") (pintype "passive"))
      (node (ref "T2") (pin "2") (pinfunction "D_2") (pintype "passive"))
      (node (ref "U4") (pin "P$4") (pinfunction "L+_P$4") (pintype "bidirectional"))
    )
    (net (code "6") (name "-24V") (class "Default")
      (node (ref "C19") (pin "P$2") (pinfunction "P$2_P$2") (pintype "passive"))
      (node (ref "C9") (pin "P$1") (pinfunction "1_P$1") (pintype "passive"))
      (node (ref "JP3") (pin "1") (pinfunction "1_1") (pintype "passive"))
      (node (ref "U1") (pin "EN") (pinfunction "EN_EN") (pintype "bidirectional"))
      (node (ref "U1") (pin "IN") (pinfunction "IN_IN") (pintype "bidirectional"))
    )
    (net (code "7") (name "AMP_POW") (class "Default")
      (node (ref "C11") (pin "P$1") (pinfunction "1_P$1") (pintype "passive"))
      (node (ref "C18") (pin "P$2") (pinfunction "2_P$2") (pintype "passive"))
      (node (ref "C29") (pin "P$2") (pinfunction "2_P$2") (pintype "passive"))
      (node (ref "C8") (pin "P$1") (pinfunction "1_P$1") (pintype "passive"))
      (node (ref "R5") (pin "P$2") (pinfunction "2_P$2") (pintype "passive"))
      (node (ref "R6") (pin "P$2") (pinfunction "2_P$2") (pintype "passive"))
      (node (ref "T2") (pin "3") (pinfunction "S_3") (pintype "passive"))
      (node (ref "U1") (pin "OUT") (pinfunction "OUT_OUT") (pintype "bidirectional"))
      (node (ref "U3") (pin "2") (pinfunction "V-_2") (pintype "power_in"))
      (node (ref "U8") (pin "2") (pinfunction "V-_2") (pintype "power_in"))
    )
    (net (code "8") (name "GND") (class "Default")
      (node (ref "C1") (pin "P$2") (pinfunction "2_P$2") (pintype "passive"))
      (node (ref "C10") (pin "P$2") (pinfunction "2_P$2") (pintype "passive"))
      (node (ref "C12") (pin "P$2") (pinfunction "2_P$2") (pintype "passive"))
      (node (ref "C13") (pin "P$2") (pinfunction "2_P$2") (pintype "passive"))
      (node (ref "C14") (pin "P$2") (pinfunction "2_P$2") (pintype "passive"))
      (node (ref "C15") (pin "P$2") (pinfunction "2_P$2") (pintype "passive"))
      (node (ref "C16") (pin "P$2") (pinfunction "2_P$2") (pintype "passive"))
      (node (ref "C17") (pin "P$2") (pinfunction "2_P$2") (pintype "passive"))
      (node (ref "C18") (pin "P$1") (pinfunction "1_P$1") (pintype "passive"))
      (node (ref "C19") (pin "P$1") (pinfunction "P$1_P$1") (pintype "passive"))
      (node (ref "C2") (pin "P$2") (pinfunction "2_P$2") (pintype "passive"))
      (node (ref "C20") (pin "P$2") (pinfunction "P$2_P$2") (pintype "passive"))
      (node (ref "C21") (pin "P$1") (pinfunction "1_P$1") (pintype "passive"))
      (node (ref "C22") (pin "P$1") (pinfunction "1_P$1") (pintype "passive"))
      (node (ref "C25") (pin "P$2") (pinfunction "2_P$2") (pintype "passive"))
      (node (ref "C26") (pin "P$2") (pinfunction "2_P$2") (pintype "passive"))
      (node (ref "C27") (pin "P$1") (pinfunction "1_P$1") (pintype "passive"))
      (node (ref "C28") (pin "P$2") (pinfunction "2_P$2") (pintype "passive"))
      (node (ref "C29") (pin "P$1") (pinfunction "1_P$1") (pintype "passive"))
      (node (ref "C3") (pin "P$2") (pinfunction "2_P$2") (pintype "passive"))
      (node (ref "C4") (pin "P$2") (pinfunction "2_P$2") (pintype "passive"))
      (node (ref "C6") (pin "P$2") (pinfunction "2_P$2") (pintype "passive"))
      (node (ref "C7") (pin "P$2") (pinfunction "2_P$2") (pintype "passive"))
      (node (ref "C8") (pin "P$2") (pinfunction "2_P$2") (pintype "passive"))
      (node (ref "C9") (pin "P$2") (pinfunction "2_P$2") (pintype "passive"))
      (node (ref "D3") (pin "CATHODE") (pinfunction "CATHODE_CATHODE") (pintype "power_in"))
      (node (ref "D4") (pin "CATHODE") (pinfunction "CATHODE_CATHODE") (pintype "power_in"))
      (node (ref "D5") (pin "CATHODE") (pinfunction "CATHODE_CATHODE") (pintype "power_in"))
      (node (ref "J1") (pin "P$2") (pinfunction "GND1_P$2") (pintype "bidirectional"))
      (node (ref "J1") (pin "P$3") (pinfunction "GND_P$3") (pintype "bidirectional"))
      (node (ref "J1") (pin "P$4") (pinfunction "GND2_P$4") (pintype "bidirectional"))
      (node (ref "J1") (pin "P$5") (pinfunction "GND3_P$5") (pintype "bidirectional"))
      (node (ref "J2") (pin "P$2") (pinfunction "GND1_P$2") (pintype "bidirectional"))
      (node (ref "J2") (pin "P$3") (pinfunction "GND_P$3") (pintype "bidirectional"))
      (node (ref "J2") (pin "P$4") (pinfunction "GND2_P$4") (pintype "bidirectional"))
      (node (ref "J2") (pin "P$5") (pinfunction "GND3_P$5") (pintype "bidirectional"))
      (node (ref "JP2") (pin "2") (pinfunction "2_2") (pintype "passive"))
      (node (ref "JP3") (pin "2") (pinfunction "2_2") (pintype "passive"))
      (node (ref "R1") (pin "P$1") (pinfunction "1_P$1") (pintype "passive"))
      (node (ref "R15") (pin "P$1") (pinfunction "1_P$1") (pintype "passive"))
      (node (ref "R18") (pin "P$2") (pinfunction "2_P$2") (pintype "passive"))
      (node (ref "R20") (pin "P$2") (pinfunction "2_P$2") (pintype "passive"))
      (node (ref "R24") (pin "P$2") (pinfunction "2_P$2") (pintype "passive"))
      (node (ref "R28") (pin "P$2") (pinfunction "2_P$2") (pintype "passive"))
      (node (ref "R36") (pin "P$1") (pinfunction "1_P$1") (pintype "passive"))
      (node (ref "R37") (pin "P$2") (pinfunction "2_P$2") (pintype "passive"))
      (node (ref "R4") (pin "P$1") (pinfunction "1_P$1") (pintype "passive"))
      (node (ref "R40") (pin "P$1") (pinfunction "1_P$1") (pintype "passive"))
      (node (ref "R41") (pin "P$1") (pinfunction "1_P$1") (pintype "passive"))
      (node (ref "R42") (pin "P$1") (pinfunction "1_P$1") (pintype "passive"))
      (node (ref "R7") (pin "P$1") (pinfunction "1_P$1") (pintype "passive"))
      (node (ref "R9") (pin "P$1") (pinfunction "1_P$1") (pintype "passive"))
      (node (ref "U1") (pin "GND") (pinfunction "GND_GND") (pintype "bidirectional"))
      (node (ref "U1") (pin "GND1") (pinfunction "GND_GND1") (pintype "bidirectional"))
      (node (ref "U10") (pin "P$2") (pinfunction "SOURCE_P$2") (pintype "bidirectional"))
      (node (ref "U2") (pin "1") (pinfunction "GND_1") (pintype "power_in"))
      (node (ref "U2") (pin "10") (pinfunction "GND_10") (pintype "power_in"))
      (node (ref "U2") (pin "11") (pinfunction "GND_11") (pintype "power_in"))
      (node (ref "U2") (pin "12") (pinfunction "GND_12") (pintype "power_in"))
      (node (ref "U2") (pin "13") (pinfunction "GND_13") (pintype "power_in"))
      (node (ref "U2") (pin "14") (pinfunction "GND_14") (pintype "power_in"))
      (node (ref "U2") (pin "15") (pinfunction "GND_15") (pintype "power_in"))
      (node (ref "U2") (pin "16") (pinfunction "GND_16") (pintype "power_in"))
      (node (ref "U2") (pin "17") (pinfunction "GND_17") (pintype "power_in"))
      (node (ref "U2") (pin "18") (pinfunction "GND_18") (pintype "power_in"))
      (node (ref "U2") (pin "19") (pinfunction "GND_19") (pintype "power_in"))
      (node (ref "U2") (pin "2") (pinfunction "GND_2") (pintype "power_in"))
      (node (ref "U2") (pin "22") (pinfunction "GND_22") (pintype "power_in"))
      (node (ref "U2") (pin "23") (pinfunction "GND_23") (pintype "power_in"))
      (node (ref "U2") (pin "24") (pinfunction "GND_24") (pintype "power_in"))
      (node (ref "U2") (pin "25") (pinfunction "GND_25") (pintype "power_in"))
      (node (ref "U2") (pin "26") (pinfunction "GND_26") (pintype "power_in"))
      (node (ref "U2") (pin "27") (pinfunction "GND_27") (pintype "power_in"))
      (node (ref "U2") (pin "28") (pinfunction "GND_28") (pintype "power_in"))
      (node (ref "U2") (pin "29") (pinfunction "GND_29") (pintype "power_in"))
      (node (ref "U2") (pin "3") (pinfunction "GND_3") (pintype "power_in"))
      (node (ref "U2") (pin "30") (pinfunction "GND_30") (pintype "power_in"))
      (node (ref "U2") (pin "31") (pinfunction "GND_31") (pintype "power_in"))
      (node (ref "U2") (pin "32") (pinfunction "GND_32") (pintype "power_in"))
      (node (ref "U2") (pin "33") (pinfunction "GND_33") (pintype "power_in"))
      (node (ref "U2") (pin "34") (pinfunction "GND_34") (pintype "power_in"))
      (node (ref "U2") (pin "35") (pinfunction "GND_35") (pintype "power_in"))
      (node (ref "U2") (pin "36") (pinfunction "GND_36") (pintype "power_in"))
      (node (ref "U2") (pin "37") (pinfunction "GND_37") (pintype "power_in"))
      (node (ref "U2") (pin "38") (pinfunction "GND_38") (pintype "power_in"))
      (node (ref "U2") (pin "39") (pinfunction "GND_39") (pintype "power_in"))
      (node (ref "U2") (pin "40") (pinfunction "GND_40") (pintype "power_in"))
      (node (ref "U2") (pin "41") (pinfunction "GND_41") (pintype "power_in"))
      (node (ref "U2") (pin "42") (pinfunction "GND_42") (pintype "power_in"))
      (node (ref "U2") (pin "6") (pinfunction "GND_6") (pintype "power_in"))
      (node (ref "U2") (pin "7") (pinfunction "GND_7") (pintype "power_in"))
      (node (ref "U2") (pin "8") (pinfunction "GND_8") (pintype "power_in"))
      (node (ref "U2") (pin "9") (pinfunction "GND_9") (pintype "power_in"))
      (node (ref "U3") (pin "3") (pinfunction "+IN_3") (pintype "input"))
      (node (ref "U4") (pin "P$2") (pinfunction "C-_P$2") (pintype "bidirectional"))
      (node (ref "U5") (pin "2") (pinfunction "V-_2") (pintype "power_in"))
      (node (ref "U6") (pin "13") (pinfunction "GND_13") (pintype "power_in"))
      (node (ref "U7") (pin "2") (pinfunction "C-_2") (pintype "bidirectional"))
      (node (ref "U8") (pin "5") (pinfunction "V+_5") (pintype "power_in"))
      (node (ref "U9") (pin "P$2") (pinfunction "SOURCE_P$2") (pintype "bidirectional"))
      (node (ref "X3") (pin "2") (pinfunction "2_2") (pintype "passive"))
    )
    (net (code "9") (name "Net-(C5-1)") (class "Default")
      (node (ref "C5") (pin "P$1") (pinfunction "1_P$1") (pintype "passive"))
      (node (ref "R37") (pin "P$1") (pinfunction "1_P$1") (pintype "passive"))
      (node (ref "R38") (pin "P$1") (pinfunction "1_P$1") (pintype "passive"))
      (node (ref "U8") (pin "4") (pinfunction "-IN_4") (pintype "input"))
    )
    (net (code "10") (name "Net-(C10-1)") (class "Default")
      (node (ref "C10") (pin "P$1") (pinfunction "1_P$1") (pintype "passive"))
      (node (ref "U1") (pin "NR/SS") (pinfunction "NR_NR/SS") (pintype "bidirectional"))
    )
    (net (code "11") (name "Net-(C11-2)") (class "Default")
      (node (ref "C11") (pin "P$2") (pinfunction "2_P$2") (pintype "passive"))
      (node (ref "R6") (pin "P$1") (pinfunction "1_P$1") (pintype "passive"))
      (node (ref "R7") (pin "P$2") (pinfunction "2_P$2") (pintype "passive"))
      (node (ref "U1") (pin "FB") (pinfunction "FB_FB") (pintype "bidirectional"))
    )
    (net (code "12") (name "Net-(C13-1)") (class "Default")
      (node (ref "C13") (pin "P$1") (pinfunction "1_P$1") (pintype "passive"))
      (node (ref "IC1") (pin "2") (pinfunction "SET_2") (pintype "bidirectional"))
      (node (ref "R1") (pin "P$2") (pinfunction "2_P$2") (pintype "passive"))
    )
    (net (code "13") (name "Net-(C15-1)") (class "Default")
      (node (ref "C15") (pin "P$1") (pinfunction "1_P$1") (pintype "passive"))
      (node (ref "U6") (pin "12") (pinfunction "PGT_12") (pintype "passive"))
    )
    (net (code "14") (name "Net-(C16-1)") (class "Default")
      (node (ref "C16") (pin "P$1") (pinfunction "1_P$1") (pintype "passive"))
      (node (ref "U6") (pin "14") (pinfunction "TMR_14") (pintype "passive"))
    )
    (net (code "15") (name "Net-(C23-1)") (class "Default")
      (node (ref "C23") (pin "P$1") (pinfunction "1_P$1") (pintype "passive"))
      (node (ref "J1") (pin "P$1") (pinfunction "P$1_P$1") (pintype "bidirectional"))
    )
    (net (code "16") (name "Net-(C23-2)") (class "Default")
      (node (ref "C23") (pin "P$2") (pinfunction "2_P$2") (pintype "passive"))
      (node (ref "C25") (pin "P$1") (pinfunction "1_P$1") (pintype "passive"))
      (node (ref "L1") (pin "P$2") (pinfunction "2_P$2") (pintype "passive"))
    )
    (net (code "17") (name "Net-(C24-1)") (class "Default")
      (node (ref "C24") (pin "P$1") (pinfunction "1_P$1") (pintype "passive"))
      (node (ref "C26") (pin "P$1") (pinfunction "1_P$1") (pintype "passive"))
      (node (ref "L2") (pin "P$1") (pinfunction "1_P$1") (pintype "passive"))
    )
    (net (code "18") (name "Net-(C24-2)") (class "Default")
      (node (ref "C24") (pin "P$2") (pinfunction "2_P$2") (pintype "passive"))
      (node (ref "J2") (pin "P$1") (pinfunction "P$1_P$1") (pintype "bidirectional"))
    )
    (net (code "19") (name "Net-(C27-2)") (class "Default")
      (node (ref "C27") (pin "P$2") (pinfunction "2_P$2") (pintype "passive"))
      (node (ref "R30") (pin "P$2") (pinfunction "2_P$2") (pintype "passive"))
      (node (ref "U8") (pin "3") (pinfunction "+IN_3") (pintype "input"))
    )
    (net (code "20") (name "Net-(C28-1)") (class "Default")
      (node (ref "C28") (pin "P$1") (pinfunction "1_P$1") (pintype "passive"))
      (node (ref "R42") (pin "P$2") (pinfunction "2_P$2") (pintype "passive"))
      (node (ref "R43") (pin "P$2") (pinfunction "2_P$2") (pintype "passive"))
      (node (ref "U6") (pin "16") (pinfunction "ON_16") (pintype "passive"))
    )
    (net (code "21") (name "Net-(L1-1)") (class "Default")
      (node (ref "L1") (pin "P$1") (pinfunction "1_P$1") (pintype "passive"))
      (node (ref "L3") (pin "P$1") (pinfunction "1_P$1") (pintype "passive"))
      (node (ref "U2") (pin "20") (pinfunction "OUT_20") (pintype "output"))
      (node (ref "U2") (pin "21") (pinfunction "OUT_21") (pintype "output"))
    )
    (net (code "22") (name "Net-(L2-2)") (class "Default")
      (node (ref "L2") (pin "P$2") (pinfunction "2_P$2") (pintype "passive"))
      (node (ref "R8") (pin "P$2") (pinfunction "2_P$2") (pintype "passive"))
      (node (ref "U2") (pin "4") (pinfunction "IN_4") (pintype "input"))
      (node (ref "U2") (pin "5") (pinfunction "IN_5") (pintype "input"))
    )
    (net (code "23") (name "Net-(R4-2)") (class "Default")
      (node (ref "R4") (pin "P$2") (pinfunction "2_P$2") (pintype "passive"))
      (node (ref "U6") (pin "15") (pinfunction "HYS/CFG_15") (pintype "passive"))
    )
    (net (code "24") (name "Net-(R5-1)") (class "Default")
      (node (ref "Q1") (pin "C") (pinfunction "C_C") (pintype "passive"))
      (node (ref "R5") (pin "P$1") (pinfunction "1_P$1") (pintype "passive"))
      (node (ref "T2") (pin "1") (pinfunction "G_1") (pintype "passive"))
    )
    (net (code "25") (name "Net-(R9-2)") (class "Default")
      (node (ref "Q1") (pin "B") (pinfunction "B_B") (pintype "passive"))
      (node (ref "R9") (pin "P$2") (pinfunction "2_P$2") (pintype "passive"))
    )
    (net (code "26") (name "Net-(R10-1)") (class "Default")
      (node (ref "R10") (pin "P$1") (pinfunction "1_P$1") (pintype "passive"))
      (node (ref "R11") (pin "P$1") (pinfunction "1_P$1") (pintype "passive"))
      (node (ref "U3") (pin "4") (pinfunction "-IN_4") (pintype "input"))
    )
    (net (code "27") (name "Net-(R11-2)") (class "Default")
      (node (ref "R11") (pin "P$2") (pinfunction "2_P$2") (pintype "passive"))
      (node (ref "R12") (pin "P$1") (pinfunction "1_P$1") (pintype "passive"))
      (node (ref "U3") (pin "1") (pinfunction "OUT_1") (pintype "output"))
    )
    (net (code "28") (name "Net-(R13-1)") (class "Default")
      (node (ref "R13") (pin "P$1") (pinfunction "1_P$1") (pintype "passive"))
      (node (ref "U7") (pin "1") (pinfunction "C+_1") (pintype "bidirectional"))
    )
    (net (code "29") (name "Net-(R13-2)") (class "Default")
      (node (ref "R13") (pin "P$2") (pinfunction "2_P$2") (pintype "passive"))
      (node (ref "R34") (pin "P$1") (pinfunction "1_P$1") (pintype "passive"))
      (node (ref "T1") (pin "3") (pinfunction "S_3") (pintype "passive"))
    )
    (net (code "30") (name "Net-(R16-1)") (class "Default")
      (node (ref "R16") (pin "P$1") (pinfunction "1_P$1") (pintype "passive"))
      (node (ref "U4") (pin "P$1") (pinfunction "C+_P$1") (pintype "bidirectional"))
    )
    (net (code "31") (name "Net-(R16-2)") (class "Default")
      (node (ref "R16") (pin "P$2") (pinfunction "2_P$2") (pintype "passive"))
      (node (ref "R17") (pin "P$1") (pinfunction "1_P$1") (pintype "passive"))
      (node (ref "R35") (pin "P$1") (pinfunction "1_P$1") (pintype "passive"))
      (node (ref "T3") (pin "3") (pinfunction "S_3") (pintype "passive"))
    )
    (net (code "32") (name "Net-(R19-2)") (class "Default")
      (node (ref "R19") (pin "P$2") (pinfunction "2_P$2") (pintype "passive"))
      (node (ref "R21") (pin "1") (pinfunction "1_1") (pintype "passive"))
    )
    (net (code "33") (name "Net-(R20-1)") (class "Default")
      (node (ref "R20") (pin "P$1") (pinfunction "1_P$1") (pintype "passive"))
      (node (ref "R21") (pin "3") (pinfunction "3_3") (pintype "passive"))
    )
    (net (code "34") (name "Net-(R22-1)") (class "Default")
      (node (ref "JP2") (pin "1") (pinfunction "1_1") (pintype "passive"))
      (node (ref "R22") (pin "P$1") (pinfunction "1_P$1") (pintype "passive"))
    )
    (net (code "35") (name "Net-(R22-2)") (class "Default")
      (node (ref "R22") (pin "P$2") (pinfunction "2_P$2") (pintype "passive"))
      (node (ref "R23") (pin "P$1") (pinfunction "1_P$1") (pintype "passive"))
      (node (ref "R33") (pin "P$1") (pinfunction "1_P$1") (pintype "passive"))
      (node (ref "T4") (pin "3") (pinfunction "S_3") (pintype "passive"))
    )
    (net (code "36") (name "Net-(R25-1)") (class "Default")
      (node (ref "R25") (pin "P$1") (pinfunction "1_P$1") (pintype "passive"))
      (node (ref "R29") (pin "P$1") (pinfunction "V$1_P$1") (pintype "passive"))
    )
    (net (code "37") (name "Net-(R25-2)") (class "Default")
      (node (ref "R25") (pin "P$2") (pinfunction "2_P$2") (pintype "passive"))
      (node (ref "T5") (pin "2") (pinfunction "D_2") (pintype "passive"))
      (node (ref "T5") (pin "4") (pinfunction "D_4") (pintype "passive"))
      (node (ref "U5") (pin "3") (pinfunction "+IN_3") (pintype "input"))
    )
    (net (code "38") (name "Net-(R26-1)") (class "Default")
      (node (ref "R26") (pin "P$1") (pinfunction "1_P$1") (pintype "passive"))
      (node (ref "U5") (pin "4") (pinfunction "-IN_4") (pintype "input"))
    )
    (net (code "39") (name "Net-(R27-1)") (class "Default")
      (node (ref "R27") (pin "P$1") (pinfunction "1_P$1") (pintype "passive"))
      (node (ref "T5") (pin "1") (pinfunction "G_1") (pintype "passive"))
    )
    (net (code "40") (name "Net-(R27-2)") (class "Default")
      (node (ref "R27") (pin "P$2") (pinfunction "2_P$2") (pintype "passive"))
      (node (ref "U5") (pin "1") (pinfunction "OUT_1") (pintype "output"))
    )
    (net (code "41") (name "Net-(R28-1)") (class "Default")
      (node (ref "R28") (pin "P$1") (pinfunction "1_P$1") (pintype "passive"))
      (node (ref "T5") (pin "3") (pinfunction "S_3") (pintype "passive"))
      (node (ref "X3") (pin "1") (pinfunction "1_1") (pintype "passive"))
    )
    (net (code "42") (name "Net-(R31-2)") (class "Default")
      (node (ref "D1") (pin "ANODE") (pinfunction "ANODE_ANODE") (pintype "power_in"))
      (node (ref "R31") (pin "P$2") (pinfunction "2_P$2") (pintype "passive"))
    )
    (net (code "43") (name "Net-(R32-2)") (class "Default")
      (node (ref "D2") (pin "ANODE") (pinfunction "ANODE_ANODE") (pintype "power_in"))
      (node (ref "R32") (pin "P$2") (pinfunction "2_P$2") (pintype "passive"))
    )
    (net (code "44") (name "Net-(R33-2)") (class "Default")
      (node (ref "D3") (pin "ANODE") (pinfunction "ANODE_ANODE") (pintype "power_in"))
      (node (ref "R33") (pin "P$2") (pinfunction "2_P$2") (pintype "passive"))
    )
    (net (code "45") (name "Net-(R34-2)") (class "Default")
      (node (ref "D4") (pin "ANODE") (pinfunction "ANODE_ANODE") (pintype "power_in"))
      (node (ref "R34") (pin "P$2") (pinfunction "2_P$2") (pintype "passive"))
    )
    (net (code "46") (name "Net-(R35-2)") (class "Default")
      (node (ref "D5") (pin "ANODE") (pinfunction "ANODE_ANODE") (pintype "power_in"))
      (node (ref "R35") (pin "P$2") (pinfunction "2_P$2") (pintype "passive"))
    )
    (net (code "47") (name "Net-(R36-2)") (class "Default")
      (node (ref "D6") (pin "ANODE") (pinfunction "ANODE_ANODE") (pintype "power_in"))
      (node (ref "R36") (pin "P$2") (pinfunction "2_P$2") (pintype "passive"))
    )
    (net (code "48") (name "Net-(R43-1)") (class "Default")
      (node (ref "JP1") (pin "2") (pinfunction "2_2") (pintype "passive"))
      (node (ref "R43") (pin "P$1") (pinfunction "1_P$1") (pintype "passive"))
    )
    (net (code "49") (name "Net-(U9-DRAIN)") (class "Default")
      (node (ref "D2") (pin "CATHODE") (pinfunction "CATHODE_CATHODE") (pintype "power_in"))
      (node (ref "U9") (pin "P$3") (pinfunction "DRAIN_P$3") (pintype "bidirectional"))
    )
    (net (code "50") (name "Net-(U10-DRAIN)") (class "Default")
      (node (ref "D1") (pin "CATHODE") (pinfunction "CATHODE_CATHODE") (pintype "power_in"))
      (node (ref "U10") (pin "P$3") (pinfunction "DRAIN_P$3") (pintype "bidirectional"))
    )
    (net (code "51") (name "RF_DET") (class "Default")
      (node (ref "R23") (pin "P$2") (pinfunction "2_P$2") (pintype "passive"))
      (node (ref "R24") (pin "P$1") (pinfunction "1_P$1") (pintype "passive"))
      (node (ref "U6") (pin "4") (pinfunction "IN4_4") (pintype "input"))
    )
    (net (code "52") (name "RF_EN") (class "Default")
      (node (ref "T4") (pin "1") (pinfunction "G_1") (pintype "passive"))
      (node (ref "U6") (pin "8") (pinfunction "OUT4_8") (pintype "output"))
    )
    (net (code "53") (name "VDD") (class "Default")
      (node (ref "C21") (pin "P$2") (pinfunction "2_P$2") (pintype "passive"))
      (node (ref "R14") (pin "P$1") (pinfunction "1_P$1") (pintype "passive"))
      (node (ref "R29") (pin "P$3") (pinfunction "I$1_P$3") (pintype "passive"))
      (node (ref "R40") (pin "P$2") (pinfunction "2_P$2") (pintype "passive"))
      (node (ref "R41") (pin "P$2") (pinfunction "2_P$2") (pintype "passive"))
      (node (ref "U7") (pin "4") (pinfunction "L-_4") (pintype "bidirectional"))
    )
    (net (code "54") (name "VDD_2") (class "Default")
      (node (ref "C2") (pin "P$1") (pinfunction "1_P$1") (pintype "passive"))
      (node (ref "C3") (pin "P$1") (pinfunction "1_P$1") (pintype "passive"))
      (node (ref "C6") (pin "P$1") (pinfunction "1_P$1") (pintype "passive"))
      (node (ref "L3") (pin "P$2") (pinfunction "2_P$2") (pintype "passive"))
      (node (ref "R29") (pin "P$4") (pinfunction "I$2_P$4") (pintype "passive"))
    )
    (net (code "55") (name "VDD_DET") (class "Default")
      (node (ref "R14") (pin "P$2") (pinfunction "2_P$2") (pintype "passive"))
      (node (ref "R15") (pin "P$2") (pinfunction "2_P$2") (pintype "passive"))
      (node (ref "U6") (pin "2") (pinfunction "IN2_2") (pintype "input"))
    )
    (net (code "56") (name "VDD_EN") (class "Default")
      (node (ref "T1") (pin "1") (pinfunction "G_1") (pintype "passive"))
      (node (ref "U6") (pin "6") (pinfunction "OUT2_6") (pintype "output"))
    )
    (net (code "57") (name "VGG") (class "Default")
      (node (ref "C4") (pin "P$1") (pinfunction "1_P$1") (pintype "passive"))
      (node (ref "C7") (pin "P$1") (pinfunction "1_P$1") (pintype "passive"))
      (node (ref "R38") (pin "P$2") (pinfunction "2_P$2") (pintype "passive"))
      (node (ref "R39") (pin "P$2") (pinfunction "2_P$2") (pintype "passive"))
      (node (ref "R8") (pin "P$1") (pinfunction "1_P$1") (pintype "passive"))
    )
    (net (code "58") (name "VGG_DET") (class "Default")
      (node (ref "R17") (pin "P$2") (pinfunction "2_P$2") (pintype "passive"))
      (node (ref "R18") (pin "P$1") (pinfunction "1_P$1") (pintype "passive"))
      (node (ref "U6") (pin "3") (pinfunction "IN3_3") (pintype "input"))
    )
    (net (code "59") (name "VGG_EN") (class "Default")
      (node (ref "T3") (pin "1") (pinfunction "G_1") (pintype "passive"))
      (node (ref "U6") (pin "7") (pinfunction "OUT3_7") (pintype "output"))
    )
    (net (code "60") (name "VL") (class "Default")
      (node (ref "R26") (pin "P$2") (pinfunction "2_P$2") (pintype "passive"))
      (node (ref "R29") (pin "P$2") (pinfunction "V$2_P$2") (pintype "passive"))
    )
    (net (code "61") (name "VMID") (class "Default")
      (node (ref "C5") (pin "P$2") (pinfunction "2_P$2") (pintype "passive"))
      (node (ref "R39") (pin "P$1") (pinfunction "1_P$1") (pintype "passive"))
      (node (ref "U8") (pin "1") (pinfunction "OUT_1") (pintype "output"))
    )
    (net (code "62") (name "VPIN_DET") (class "Default")
      (node (ref "R12") (pin "P$2") (pinfunction "2_P$2") (pintype "passive"))
      (node (ref "U6") (pin "1") (pinfunction "IN1_1") (pintype "input"))
    )
    (net (code "63") (name "VPIN_EN") (class "Default")
      (node (ref "Q1") (pin "E") (pinfunction "E_E") (pintype "passive"))
      (node (ref "U6") (pin "5") (pinfunction "OUT1_5") (pintype "output"))
    )
    (net (code "64") (name "V_PINCH") (class "Default")
      (node (ref "R21") (pin "2") (pinfunction "2_2") (pintype "passive"))
      (node (ref "R30") (pin "P$1") (pinfunction "1_P$1") (pintype "passive"))
      (node (ref "U4") (pin "P$3") (pinfunction "L-_P$3") (pintype "bidirectional"))
    )
  )
)
